# Frontboard_TIC.net
KiCad netlist of a schematic drawn in EAGLE
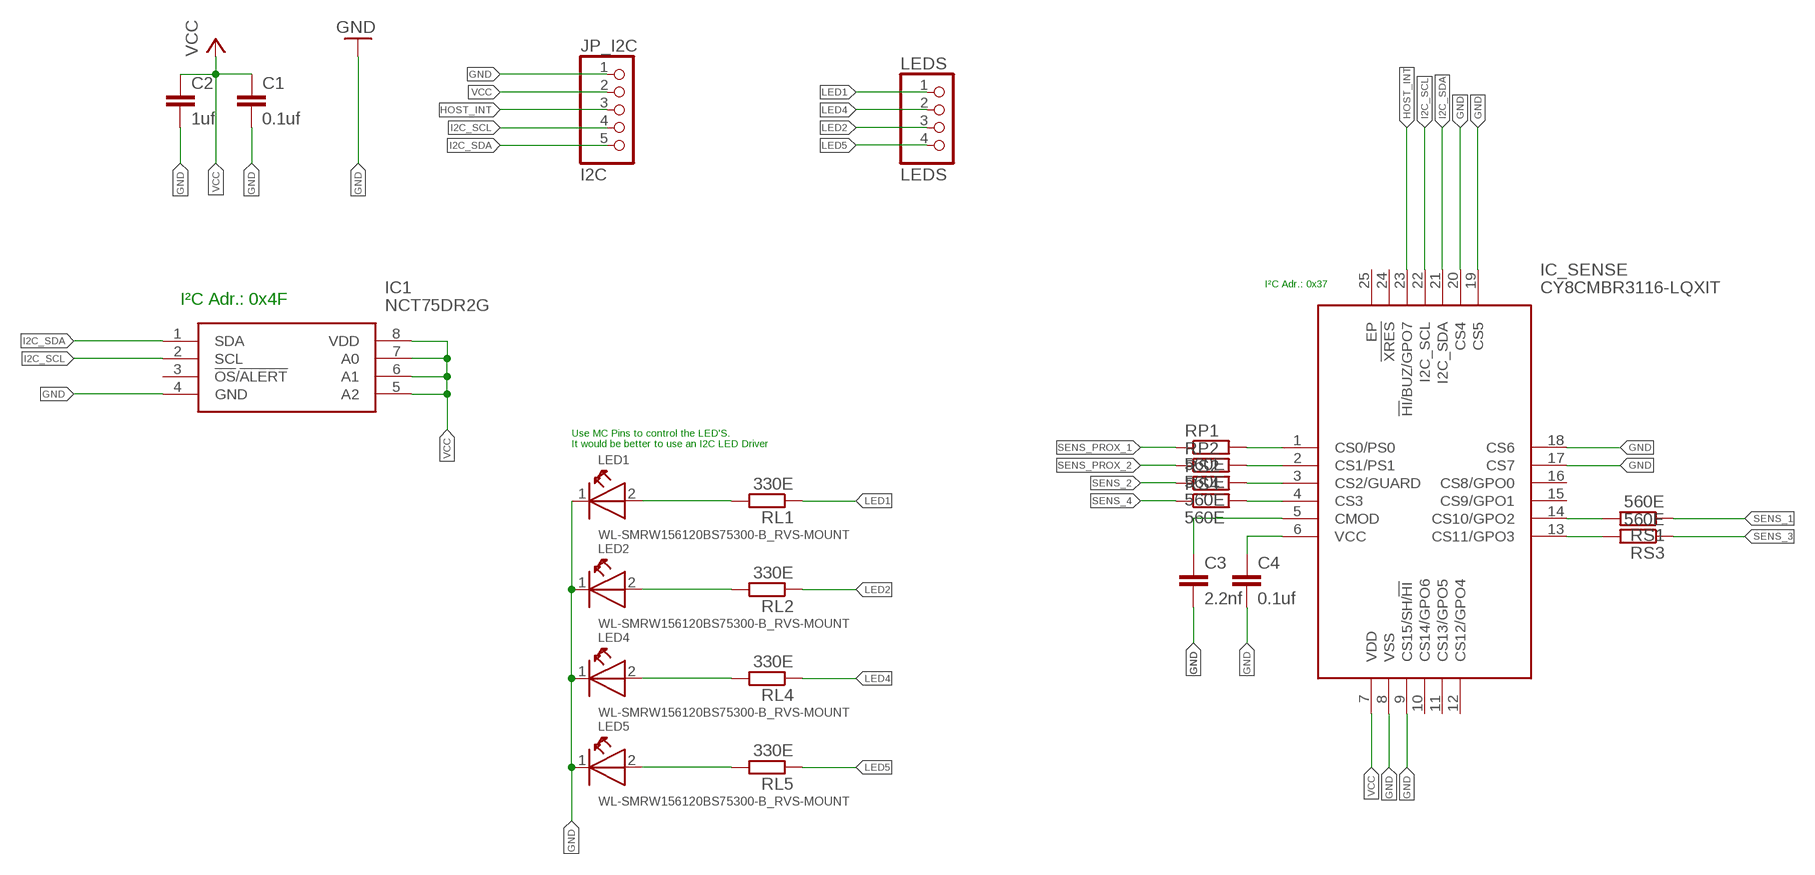
[diagram p0: schematic, sheet 1]

(export (version "E")
  (design (tool "Eeschema 10.0.6"))
  (components
    (comp (ref "C1")
      (value "0.1uf")
      (footprint "eagle-import:C0805")
      (libsource (lib "eagle-import") (part "C-EUC0805"))
    )
    (comp (ref "C2")
      (value "1uf")
      (footprint "eagle-import:C0805")
      (libsource (lib "eagle-import") (part "C-EUC0805"))
    )
    (comp (ref "C3")
      (value "2.2nf")
      (footprint "eagle-import:C0805")
      (libsource (lib "eagle-import") (part "C-EUC0805"))
    )
    (comp (ref "C4")
      (value "0.1uf")
      (footprint "eagle-import:C0805")
      (libsource (lib "eagle-import") (part "C-EUC0805"))
    )
    (comp (ref "IC1")
      (value "NCT75DR2G")
      (footprint "eagle-import:SOIC127P600X175-8N")
      (fields (field (name "RS_PART_NUMBER") "8051854P"))
      (libsource (lib "eagle-import") (part "NCT75DR2G"))
    )
    (comp (ref "IC_SENSE")
      (value "CY8CMBR3116-LQXIT")
      (footprint "eagle-import:QFN50P400X400X60-25N")
      (libsource (lib "eagle-import") (part "CY8CMBR3116-LQXIT"))
    )
    (comp (ref "JP_I2C")
      (value "I2C")
      (footprint "eagle-import:1X05SMD")
      (libsource (lib "eagle-import") (part "PINHD-1X5_2.54-SMD"))
    )
    (comp (ref "LED1")
      (value "WL-SMRW156120BS75300-B_RVS-MOUNT")
      (footprint "eagle-import:WL-SMRW-1206-CYLDR-REVERSE-MOUNT")
      (libsource (lib "eagle-import") (part "WL-SMRW156120BS75300-B_RVS-MOUNT"))
    )
    (comp (ref "LED2")
      (value "WL-SMRW156120BS75300-B_RVS-MOUNT")
      (footprint "eagle-import:WL-SMRW-1206-CYLDR-REVERSE-MOUNT")
      (libsource (lib "eagle-import") (part "WL-SMRW156120BS75300-B_RVS-MOUNT"))
    )
    (comp (ref "LED4")
      (value "WL-SMRW156120BS75300-B_RVS-MOUNT")
      (footprint "eagle-import:WL-SMRW-1206-CYLDR-REVERSE-MOUNT")
      (libsource (lib "eagle-import") (part "WL-SMRW156120BS75300-B_RVS-MOUNT"))
    )
    (comp (ref "LED5")
      (value "WL-SMRW156120BS75300-B_RVS-MOUNT")
      (footprint "eagle-import:WL-SMRW-1206-CYLDR-REVERSE-MOUNT")
      (libsource (lib "eagle-import") (part "WL-SMRW156120BS75300-B_RVS-MOUNT"))
    )
    (comp (ref "LEDS")
      (value "LEDS")
      (footprint "eagle-import:1X04SMD")
      (libsource (lib "eagle-import") (part "PINHD-1X4_2.54-SMD"))
    )
    (comp (ref "RL1")
      (value "330E")
      (footprint "eagle-import:R0805")
      (libsource (lib "eagle-import") (part "R-EU_R0805"))
    )
    (comp (ref "RL2")
      (value "330E")
      (footprint "eagle-import:R0805")
      (libsource (lib "eagle-import") (part "R-EU_R0805"))
    )
    (comp (ref "RL4")
      (value "330E")
      (footprint "eagle-import:R0805")
      (libsource (lib "eagle-import") (part "R-EU_R0805"))
    )
    (comp (ref "RL5")
      (value "330E")
      (footprint "eagle-import:R0805")
      (libsource (lib "eagle-import") (part "R-EU_R0805"))
    )
    (comp (ref "RP1")
      (value "560E")
      (footprint "eagle-import:R0805")
      (libsource (lib "eagle-import") (part "R-EU_R0805"))
    )
    (comp (ref "RP2")
      (value "560E")
      (footprint "eagle-import:R0805")
      (libsource (lib "eagle-import") (part "R-EU_R0805"))
    )
    (comp (ref "RS1")
      (value "560E")
      (footprint "eagle-import:R0805")
      (libsource (lib "eagle-import") (part "R-EU_R0805"))
    )
    (comp (ref "RS2")
      (value "560E")
      (footprint "eagle-import:R0805")
      (libsource (lib "eagle-import") (part "R-EU_R0805"))
    )
    (comp (ref "RS3")
      (value "560E")
      (footprint "eagle-import:R0805")
      (libsource (lib "eagle-import") (part "R-EU_R0805"))
    )
    (comp (ref "RS4")
      (value "560E")
      (footprint "eagle-import:R0805")
      (libsource (lib "eagle-import") (part "R-EU_R0805"))
    )
  )
  (nets
    (net (code "1") (name "GND") (class "Default")
      (node (ref "C1") (pin "2") (pinfunction "2_2") (pintype "passive"))
      (node (ref "C2") (pin "2") (pinfunction "2_2") (pintype "passive"))
      (node (ref "C3") (pin "2") (pinfunction "2_2") (pintype "passive"))
      (node (ref "C4") (pin "2") (pinfunction "2_2") (pintype "passive"))
      (node (ref "IC1") (pin "4") (pinfunction "GND_4") (pintype "power_in"))
      (node (ref "IC_SENSE") (pin "17") (pinfunction "CS7_17") (pintype "bidirectional"))
      (node (ref "IC_SENSE") (pin "18") (pinfunction "CS6_18") (pintype "bidirectional"))
      (node (ref "IC_SENSE") (pin "19") (pinfunction "CS5_19") (pintype "bidirectional"))
      (node (ref "IC_SENSE") (pin "20") (pinfunction "CS4_20") (pintype "bidirectional"))
      (node (ref "IC_SENSE") (pin "8") (pinfunction "VSS_8") (pintype "bidirectional"))
      (node (ref "IC_SENSE") (pin "9") (pinfunction "CS15/SH/~{HI}_9") (pintype "bidirectional"))
      (node (ref "JP_I2C") (pin "1") (pinfunction "1_1") (pintype "passive"))
      (node (ref "LED1") (pin "1") (pinfunction "K_1") (pintype "bidirectional"))
      (node (ref "LED2") (pin "1") (pinfunction "K_1") (pintype "bidirectional"))
      (node (ref "LED4") (pin "1") (pinfunction "K_1") (pintype "bidirectional"))
      (node (ref "LED5") (pin "1") (pinfunction "K_1") (pintype "bidirectional"))
    )
    (net (code "2") (name "HOST_INT") (class "Default")
      (node (ref "IC_SENSE") (pin "23") (pinfunction "~{HI}/BUZ/GPO7_23") (pintype "bidirectional"))
      (node (ref "JP_I2C") (pin "3") (pinfunction "3_3") (pintype "passive"))
    )
    (net (code "3") (name "I2C_SCL") (class "Default")
      (node (ref "IC1") (pin "2") (pinfunction "SCL_2") (pintype "bidirectional"))
      (node (ref "IC_SENSE") (pin "22") (pinfunction "I2C_SCL_22") (pintype "bidirectional"))
      (node (ref "JP_I2C") (pin "4") (pinfunction "4_4") (pintype "passive"))
    )
    (net (code "4") (name "I2C_SDA") (class "Default")
      (node (ref "IC1") (pin "1") (pinfunction "SDA_1") (pintype "bidirectional"))
      (node (ref "IC_SENSE") (pin "21") (pinfunction "I2C_SDA_21") (pintype "bidirectional"))
      (node (ref "JP_I2C") (pin "5") (pinfunction "5_5") (pintype "passive"))
    )
    (net (code "5") (name "LED1") (class "Default")
      (node (ref "LEDS") (pin "1") (pinfunction "1_1") (pintype "passive"))
      (node (ref "RL1") (pin "1") (pinfunction "1_1") (pintype "passive"))
    )
    (net (code "6") (name "LED2") (class "Default")
      (node (ref "LEDS") (pin "3") (pinfunction "3_3") (pintype "passive"))
      (node (ref "RL2") (pin "1") (pinfunction "1_1") (pintype "passive"))
    )
    (net (code "7") (name "LED4") (class "Default")
      (node (ref "LEDS") (pin "2") (pinfunction "2_2") (pintype "passive"))
      (node (ref "RL4") (pin "1") (pinfunction "1_1") (pintype "passive"))
    )
    (net (code "8") (name "LED5") (class "Default")
      (node (ref "LEDS") (pin "4") (pinfunction "4_4") (pintype "passive"))
      (node (ref "RL5") (pin "1") (pinfunction "1_1") (pintype "passive"))
    )
    (net (code "9") (name "Net-(IC_SENSE-CMOD)") (class "Default")
      (node (ref "C3") (pin "1") (pinfunction "1_1") (pintype "passive"))
      (node (ref "IC_SENSE") (pin "5") (pinfunction "CMOD_5") (pintype "bidirectional"))
    )
    (net (code "10") (name "Net-(IC_SENSE-CS0{slash}PS0)") (class "Default")
      (node (ref "IC_SENSE") (pin "1") (pinfunction "CS0/PS0_1") (pintype "bidirectional"))
      (node (ref "RP1") (pin "2") (pinfunction "2_2") (pintype "passive"))
    )
    (net (code "11") (name "Net-(IC_SENSE-CS1{slash}PS1)") (class "Default")
      (node (ref "IC_SENSE") (pin "2") (pinfunction "CS1/PS1_2") (pintype "bidirectional"))
      (node (ref "RP2") (pin "2") (pinfunction "2_2") (pintype "passive"))
    )
    (net (code "12") (name "Net-(IC_SENSE-CS2{slash}GUARD)") (class "Default")
      (node (ref "IC_SENSE") (pin "3") (pinfunction "CS2/GUARD_3") (pintype "bidirectional"))
      (node (ref "RS2") (pin "2") (pinfunction "2_2") (pintype "passive"))
    )
    (net (code "13") (name "Net-(IC_SENSE-CS3)") (class "Default")
      (node (ref "IC_SENSE") (pin "4") (pinfunction "CS3_4") (pintype "bidirectional"))
      (node (ref "RS4") (pin "2") (pinfunction "2_2") (pintype "passive"))
    )
    (net (code "14") (name "Net-(IC_SENSE-CS10{slash}GPO2)") (class "Default")
      (node (ref "IC_SENSE") (pin "14") (pinfunction "CS10/GPO2_14") (pintype "bidirectional"))
      (node (ref "RS1") (pin "2") (pinfunction "2_2") (pintype "passive"))
    )
    (net (code "15") (name "Net-(IC_SENSE-CS11{slash}GPO3)") (class "Default")
      (node (ref "IC_SENSE") (pin "13") (pinfunction "CS11/GPO3_13") (pintype "bidirectional"))
      (node (ref "RS3") (pin "2") (pinfunction "2_2") (pintype "passive"))
    )
    (net (code "16") (name "Net-(IC_SENSE-VCC)") (class "Default")
      (node (ref "C4") (pin "1") (pinfunction "1_1") (pintype "passive"))
      (node (ref "IC_SENSE") (pin "6") (pinfunction "VCC_6") (pintype "bidirectional"))
    )
    (net (code "17") (name "Net-(LED1-A)") (class "Default")
      (node (ref "LED1") (pin "2") (pinfunction "A_2") (pintype "bidirectional"))
      (node (ref "RL1") (pin "2") (pinfunction "2_2") (pintype "passive"))
    )
    (net (code "18") (name "Net-(LED2-A)") (class "Default")
      (node (ref "LED2") (pin "2") (pinfunction "A_2") (pintype "bidirectional"))
      (node (ref "RL2") (pin "2") (pinfunction "2_2") (pintype "passive"))
    )
    (net (code "19") (name "Net-(LED4-A)") (class "Default")
      (node (ref "LED4") (pin "2") (pinfunction "A_2") (pintype "bidirectional"))
      (node (ref "RL4") (pin "2") (pinfunction "2_2") (pintype "passive"))
    )
    (net (code "20") (name "Net-(LED5-A)") (class "Default")
      (node (ref "LED5") (pin "2") (pinfunction "A_2") (pintype "bidirectional"))
      (node (ref "RL5") (pin "2") (pinfunction "2_2") (pintype "passive"))
    )
    (net (code "21") (name "SENS_1") (class "Default")
      (node (ref "RS1") (pin "1") (pinfunction "1_1") (pintype "passive"))
    )
    (net (code "22") (name "SENS_2") (class "Default")
      (node (ref "RS2") (pin "1") (pinfunction "1_1") (pintype "passive"))
    )
    (net (code "23") (name "SENS_3") (class "Default")
      (node (ref "RS3") (pin "1") (pinfunction "1_1") (pintype "passive"))
    )
    (net (code "24") (name "SENS_4") (class "Default")
      (node (ref "RS4") (pin "1") (pinfunction "1_1") (pintype "passive"))
    )
    (net (code "25") (name "SENS_PROX_1") (class "Default")
      (node (ref "RP1") (pin "1") (pinfunction "1_1") (pintype "passive"))
    )
    (net (code "26") (name "SENS_PROX_2") (class "Default")
      (node (ref "RP2") (pin "1") (pinfunction "1_1") (pintype "passive"))
    )
    (net (code "27") (name "VCC") (class "Default")
      (node (ref "C1") (pin "1") (pinfunction "1_1") (pintype "passive"))
      (node (ref "C2") (pin "1") (pinfunction "1_1") (pintype "passive"))
      (node (ref "IC1") (pin "5") (pinfunction "A2_5") (pintype "bidirectional"))
      (node (ref "IC1") (pin "6") (pinfunction "A1_6") (pintype "bidirectional"))
      (node (ref "IC1") (pin "7") (pinfunction "A0_7") (pintype "bidirectional"))
      (node (ref "IC1") (pin "8") (pinfunction "VDD_8") (pintype "power_in"))
      (node (ref "IC_SENSE") (pin "7") (pinfunction "VDD_7") (pintype "bidirectional"))
      (node (ref "JP_I2C") (pin "2") (pinfunction "2_2") (pintype "passive"))
    )
    (net (code "28") (name "unconnected-(IC1-~{OS}{slash}~{ALERT}-Pad3)") (class "Default")
      (node (ref "IC1") (pin "3") (pinfunction "~{OS}/~{ALERT}_3") (pintype "bidirectional"))
    )
    (net (code "29") (name "unconnected-(IC_SENSE-CS8{slash}GPO0-Pad16)") (class "Default")
      (node (ref "IC_SENSE") (pin "16") (pinfunction "CS8/GPO0_16") (pintype "bidirectional"))
    )
    (net (code "30") (name "unconnected-(IC_SENSE-CS9{slash}GPO1-Pad15)") (class "Default")
      (node (ref "IC_SENSE") (pin "15") (pinfunction "CS9/GPO1_15") (pintype "bidirectional"))
    )
    (net (code "31") (name "unconnected-(IC_SENSE-CS12{slash}GPO4-Pad12)") (class "Default")
      (node (ref "IC_SENSE") (pin "12") (pinfunction "CS12/GPO4_12") (pintype "bidirectional"))
    )
    (net (code "32") (name "unconnected-(IC_SENSE-CS13{slash}GPO5-Pad11)") (class "Default")
      (node (ref "IC_SENSE") (pin "11") (pinfunction "CS13/GPO5_11") (pintype "bidirectional"))
    )
    (net (code "33") (name "unconnected-(IC_SENSE-CS14{slash}GPO6-Pad10)") (class "Default")
      (node (ref "IC_SENSE") (pin "10") (pinfunction "CS14/GPO6_10") (pintype "bidirectional"))
    )
    (net (code "34") (name "unconnected-(IC_SENSE-EP-Pad25)") (class "Default")
      (node (ref "IC_SENSE") (pin "25") (pinfunction "EP_25") (pintype "bidirectional"))
    )
    (net (code "35") (name "unconnected-(IC_SENSE-~{XRES}-Pad24)") (class "Default")
      (node (ref "IC_SENSE") (pin "24") (pinfunction "~{XRES}_24") (pintype "bidirectional"))
    )
  )
)
